# Power_BE.net
KiCad netlist of a schematic drawn in Altium Designer
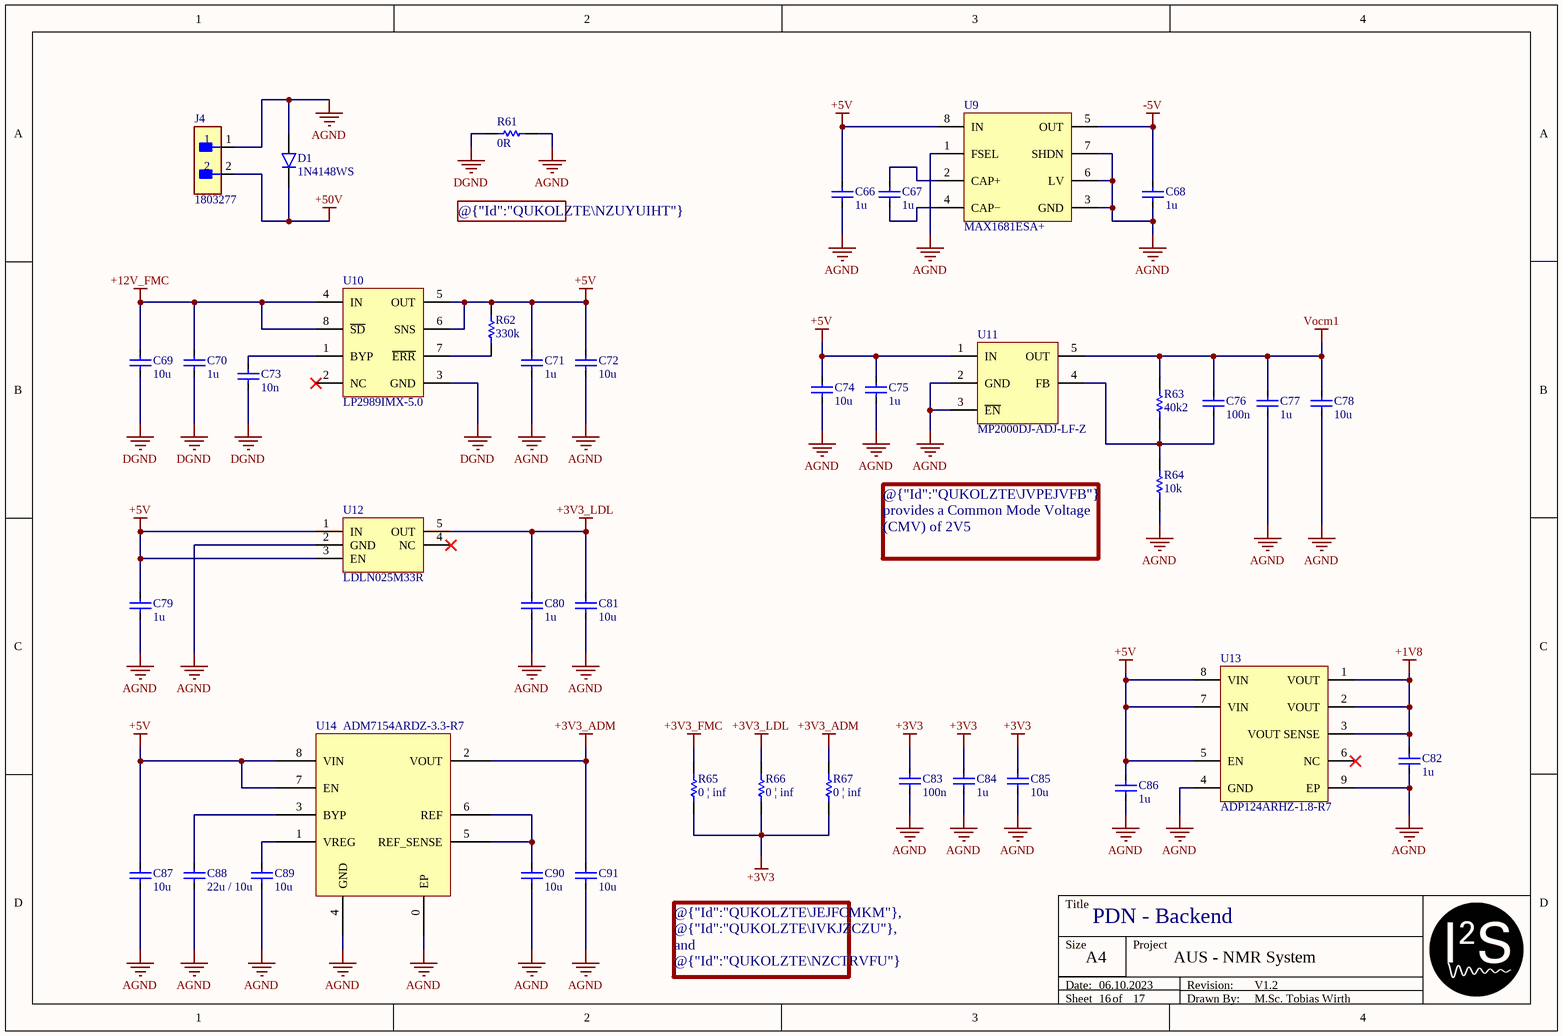
[diagram p0: Power_BE.SchDoc]

(export (version "E")
  (design (tool "Eeschema 10.0.6"))
  (components
    (comp (ref "C66") (value "1u") (footprint "CAP_0402") (libsource (lib "IIS-Lib_TW") (part "Cap")))
    (comp (ref "C67") (value "1u") (footprint "CAP_0402") (libsource (lib "IIS-Lib_TW") (part "Cap")))
    (comp (ref "C68") (value "1u") (footprint "CAP_0402") (libsource (lib "IIS-Lib_TW") (part "Cap")))
    (comp (ref "C69") (value "10u") (footprint "CAP_0603") (libsource (lib "IIS-Lib_TW") (part "Cap")))
    (comp (ref "C70") (value "1u") (footprint "CAP_0402") (libsource (lib "IIS-Lib_TW") (part "Cap")))
    (comp (ref "C71") (value "1u") (footprint "CAP_0402") (libsource (lib "IIS-Lib_TW") (part "Cap")))
    (comp (ref "C72") (value "10u") (footprint "CAP_0603") (libsource (lib "IIS-Lib_TW") (part "Cap")))
    (comp (ref "C73") (value "10n") (footprint "CAP_0402") (libsource (lib "IIS-Lib_TW") (part "Cap")))
    (comp (ref "C74") (value "10u") (footprint "CAP_0603") (libsource (lib "IIS-Lib_TW") (part "Cap")))
    (comp (ref "C75") (value "1u") (footprint "CAP_0402") (libsource (lib "IIS-Lib_TW") (part "Cap")))
    (comp (ref "C76") (value "100n") (footprint "CAP_0402") (libsource (lib "IIS-Lib_TW") (part "Cap")))
    (comp (ref "C77") (value "1u") (footprint "CAP_0402") (libsource (lib "IIS-Lib_TW") (part "Cap")))
    (comp (ref "C78") (value "10u") (footprint "CAP_0603") (libsource (lib "IIS-Lib_TW") (part "Cap")))
    (comp (ref "C79") (value "1u") (footprint "CAP_0402") (libsource (lib "IIS-Lib_TW") (part "Cap")))
    (comp (ref "C80") (value "1u") (footprint "CAP_0402") (libsource (lib "IIS-Lib_TW") (part "Cap")))
    (comp (ref "C81") (value "10u") (footprint "CAP_0603") (libsource (lib "IIS-Lib_TW") (part "Cap")))
    (comp (ref "C82") (value "1u") (footprint "CAP_0402") (libsource (lib "IIS-Lib_TW") (part "Cap")))
    (comp (ref "C83") (value "100n") (footprint "CAP_0402") (libsource (lib "IIS-Lib_TW") (part "Cap")))
    (comp (ref "C84") (value "1u") (footprint "CAP_0402") (libsource (lib "IIS-Lib_TW") (part "Cap")))
    (comp (ref "C85") (value "10u") (footprint "CAP_0603") (libsource (lib "IIS-Lib_TW") (part "Cap")))
    (comp (ref "C86") (value "1u") (footprint "CAP_0402") (libsource (lib "IIS-Lib_TW") (part "Cap")))
    (comp (ref "C87")
      (value "10u")
      (footprint "IIS-Lib_TW:CAP_0603")
      (libsource (lib "IIS-Lib_TW") (part "Cap"))
    )
    (comp (ref "C88")
      (value "22u / 10u")
      (footprint "IIS-Lib_TW:CAP_0603")
      (libsource (lib "IIS-Lib_TW") (part "Cap"))
    )
    (comp (ref "C89")
      (value "10u")
      (footprint "IIS-Lib_TW:CAP_0603")
      (libsource (lib "IIS-Lib_TW") (part "Cap"))
    )
    (comp (ref "C90")
      (value "10u")
      (footprint "IIS-Lib_TW:CAP_0603")
      (libsource (lib "IIS-Lib_TW") (part "Cap"))
    )
    (comp (ref "C91")
      (value "10u")
      (footprint "IIS-Lib_TW:CAP_0603")
      (libsource (lib "IIS-Lib_TW") (part "Cap"))
    )
    (comp (ref "D1") (value "1N4148WS") (footprint "SOD-123F") (libsource (lib "IIS-Lib_TW") (part "Diode")))
    (comp (ref "J4")
      (value "1803277")
      (footprint "Phoenix_MC1,5/2-G-3,81")
      (fields (field (name "MANUFACTURER") "Phoenix Contact"))
      (libsource (lib "IIS-Lib_TW") (part "Phoenix_MC1,5/2-G-3,81"))
    )
    (comp (ref "R61")
      (value "0R")
      (footprint "RES_0402")
      (description "Net tie")
      (libsource (lib "IIS-Lib_TW") (part "Res"))
    )
    (comp (ref "R62") (value "330k") (footprint "RES_0402") (libsource (lib "IIS-Lib_TW") (part "Res")))
    (comp (ref "R63") (value "40k2") (footprint "RES_0402") (libsource (lib "IIS-Lib_TW") (part "Res")))
    (comp (ref "R64") (value "10k") (footprint "RES_0402") (libsource (lib "IIS-Lib_TW") (part "Res")))
    (comp (ref "R65") (value "0 ¦ inf") (footprint "RES_0402") (libsource (lib "IIS-Lib_TW") (part "Res")))
    (comp (ref "R66") (value "0 ¦ inf") (footprint "RES_0402") (libsource (lib "IIS-Lib_TW") (part "Res")))
    (comp (ref "R67") (value "0 ¦ inf") (footprint "RES_0402") (libsource (lib "IIS-Lib_TW") (part "Res")))
    (comp (ref "U9")
      (value "MAX1681ESA+")
      (footprint "SOP127P600X175-8N")
      (description "125mA, Frequency-Selectable, Switched-Capacitor Voltage Converters")
      (libsource (lib "IIS-Lib_TW") (part "MAX1681"))
    )
    (comp (ref "U10")
      (value "LP2989IMX-5.0")
      (footprint "SOP127P600X175-8N")
      (libsource (lib "IIS-Lib_TW") (part "LP2989"))
    )
    (comp (ref "U11")
      (value "MP2000DJ-ADJ-LF-Z")
      (footprint "SOT95P280X145-5N")
      (libsource (lib "IIS-Lib_TW") (part "MP2000"))
    )
    (comp (ref "U12")
      (value "LDLN025M33R")
      (footprint "SOT95P280X145-5N")
      (libsource (lib "IIS-Lib_TW") (part "LDLN025"))
    )
    (comp (ref "U13")
      (value "ADP124ARHZ-1.8-R7")
      (footprint "IIS-Lib_TW:TSOP65P490X94_HS-9N - TW")
      (libsource (lib "IIS-Lib_TW") (part "ADP124"))
    )
    (comp (ref "U14")
      (value "ADM7154ARDZ-3.3-R7")
      (footprint "IIS-Lib_TW:SOIC-8_TP - TW")
      (libsource (lib "IIS-Lib_TW") (part "ADM715X"))
    )
  )
  (nets
    (net (code "1") (name "+1V8") (class "Default")
      (node (ref "C82") (pin "1") (pinfunction "1_1") (pintype "passive"))
      (node (ref "U13") (pin "1") (pinfunction "VOUT_1") (pintype "passive"))
      (node (ref "U13") (pin "2") (pinfunction "VOUT_2") (pintype "passive"))
      (node (ref "U13") (pin "3") (pinfunction "VOUT_SENSE_3") (pintype "passive"))
    )
    (net (code "2") (name "+3V3") (class "Default")
      (node (ref "C83") (pin "1") (pinfunction "1_1") (pintype "passive"))
      (node (ref "C84") (pin "1") (pinfunction "1_1") (pintype "passive"))
      (node (ref "C85") (pin "1") (pinfunction "1_1") (pintype "passive"))
      (node (ref "R65") (pin "1") (pinfunction "1_1") (pintype "passive"))
      (node (ref "R66") (pin "1") (pinfunction "1_1") (pintype "passive"))
      (node (ref "R67") (pin "1") (pinfunction "1_1") (pintype "passive"))
    )
    (net (code "3") (name "+3V3_ADM") (class "Default")
      (node (ref "C91") (pin "1") (pinfunction "1_1") (pintype "passive"))
      (node (ref "R67") (pin "2") (pinfunction "2_2") (pintype "passive"))
      (node (ref "U14") (pin "2") (pinfunction "VOUT_2") (pintype "passive"))
    )
    (net (code "4") (name "+3V3_FMC") (class "Default")
      (node (ref "R65") (pin "2") (pinfunction "2_2") (pintype "passive"))
    )
    (net (code "5") (name "+3V3_LDL") (class "Default")
      (node (ref "C80") (pin "1") (pinfunction "1_1") (pintype "passive"))
      (node (ref "C81") (pin "1") (pinfunction "1_1") (pintype "passive"))
      (node (ref "R66") (pin "2") (pinfunction "2_2") (pintype "passive"))
      (node (ref "U12") (pin "5") (pinfunction "OUT_5") (pintype "passive"))
    )
    (net (code "6") (name "+5V") (class "Default")
      (node (ref "C66") (pin "1") (pinfunction "1_1") (pintype "passive"))
      (node (ref "C71") (pin "1") (pinfunction "1_1") (pintype "passive"))
      (node (ref "C72") (pin "1") (pinfunction "1_1") (pintype "passive"))
      (node (ref "C74") (pin "1") (pinfunction "1_1") (pintype "passive"))
      (node (ref "C75") (pin "1") (pinfunction "1_1") (pintype "passive"))
      (node (ref "C79") (pin "1") (pinfunction "1_1") (pintype "passive"))
      (node (ref "C86") (pin "1") (pinfunction "1_1") (pintype "passive"))
      (node (ref "C87") (pin "1") (pinfunction "1_1") (pintype "passive"))
      (node (ref "R62") (pin "2") (pinfunction "2_2") (pintype "passive"))
      (node (ref "U10") (pin "5") (pinfunction "OUT_5") (pintype "passive"))
      (node (ref "U10") (pin "6") (pinfunction "SNS_6") (pintype "passive"))
      (node (ref "U11") (pin "1") (pinfunction "IN_1") (pintype "passive"))
      (node (ref "U12") (pin "1") (pinfunction "IN_1") (pintype "passive"))
      (node (ref "U12") (pin "3") (pinfunction "EN_3") (pintype "passive"))
      (node (ref "U13") (pin "5") (pinfunction "EN_5") (pintype "passive"))
      (node (ref "U13") (pin "7") (pinfunction "VIN_7") (pintype "passive"))
      (node (ref "U13") (pin "8") (pinfunction "VIN_8") (pintype "passive"))
      (node (ref "U14") (pin "7") (pinfunction "EN_7") (pintype "passive"))
      (node (ref "U14") (pin "8") (pinfunction "VIN_8") (pintype "passive"))
      (node (ref "U9") (pin "8") (pinfunction "IN_8") (pintype "passive"))
    )
    (net (code "7") (name "+12V_FMC") (class "Default")
      (node (ref "C69") (pin "1") (pinfunction "1_1") (pintype "passive"))
      (node (ref "C70") (pin "1") (pinfunction "1_1") (pintype "passive"))
      (node (ref "U10") (pin "4") (pinfunction "IN_4") (pintype "passive"))
      (node (ref "U10") (pin "8") (pinfunction "~{SD}_8") (pintype "passive"))
    )
    (net (code "8") (name "+50V") (class "Default")
      (node (ref "D1") (pin "2") (pinfunction "2_2") (pintype "passive"))
      (node (ref "J4") (pin "2") (pinfunction "2_2") (pintype "passive"))
    )
    (net (code "9") (name "-5V") (class "Default")
      (node (ref "C68") (pin "1") (pinfunction "1_1") (pintype "passive"))
      (node (ref "U9") (pin "5") (pinfunction "OUT_5") (pintype "passive"))
    )
    (net (code "10") (name "AGND") (class "Default")
      (node (ref "C66") (pin "2") (pinfunction "2_2") (pintype "passive"))
      (node (ref "C68") (pin "2") (pinfunction "2_2") (pintype "passive"))
      (node (ref "C71") (pin "2") (pinfunction "2_2") (pintype "passive"))
      (node (ref "C72") (pin "2") (pinfunction "2_2") (pintype "passive"))
      (node (ref "C74") (pin "2") (pinfunction "2_2") (pintype "passive"))
      (node (ref "C75") (pin "2") (pinfunction "2_2") (pintype "passive"))
      (node (ref "C77") (pin "2") (pinfunction "2_2") (pintype "passive"))
      (node (ref "C78") (pin "2") (pinfunction "2_2") (pintype "passive"))
      (node (ref "C79") (pin "2") (pinfunction "2_2") (pintype "passive"))
      (node (ref "C80") (pin "2") (pinfunction "2_2") (pintype "passive"))
      (node (ref "C81") (pin "2") (pinfunction "2_2") (pintype "passive"))
      (node (ref "C82") (pin "2") (pinfunction "2_2") (pintype "passive"))
      (node (ref "C83") (pin "2") (pinfunction "2_2") (pintype "passive"))
      (node (ref "C84") (pin "2") (pinfunction "2_2") (pintype "passive"))
      (node (ref "C85") (pin "2") (pinfunction "2_2") (pintype "passive"))
      (node (ref "C86") (pin "2") (pinfunction "2_2") (pintype "passive"))
      (node (ref "C87") (pin "2") (pinfunction "2_2") (pintype "passive"))
      (node (ref "C88") (pin "2") (pinfunction "2_2") (pintype "passive"))
      (node (ref "C89") (pin "2") (pinfunction "2_2") (pintype "passive"))
      (node (ref "C90") (pin "2") (pinfunction "2_2") (pintype "passive"))
      (node (ref "C91") (pin "2") (pinfunction "2_2") (pintype "passive"))
      (node (ref "D1") (pin "1") (pinfunction "1_1") (pintype "passive"))
      (node (ref "J4") (pin "1") (pinfunction "1_1") (pintype "passive"))
      (node (ref "R61") (pin "2") (pinfunction "2_2") (pintype "passive"))
      (node (ref "R64") (pin "1") (pinfunction "1_1") (pintype "passive"))
      (node (ref "U11") (pin "2") (pinfunction "GND_2") (pintype "passive"))
      (node (ref "U11") (pin "3") (pinfunction "~{EN}_3") (pintype "passive"))
      (node (ref "U12") (pin "2") (pinfunction "GND_2") (pintype "passive"))
      (node (ref "U13") (pin "4") (pinfunction "GND_4") (pintype "passive"))
      (node (ref "U13") (pin "9") (pinfunction "EP_9") (pintype "passive"))
      (node (ref "U14") (pin "0") (pinfunction "EP_0") (pintype "passive"))
      (node (ref "U14") (pin "4") (pinfunction "GND_4") (pintype "passive"))
      (node (ref "U9") (pin "1") (pinfunction "FSEL_1") (pintype "passive"))
      (node (ref "U9") (pin "3") (pinfunction "GND_3") (pintype "passive"))
      (node (ref "U9") (pin "6") (pinfunction "LV_6") (pintype "passive"))
      (node (ref "U9") (pin "7") (pinfunction "SHDN_7") (pintype "passive"))
    )
    (net (code "11") (name "DGND") (class "Default")
      (node (ref "C69") (pin "2") (pinfunction "2_2") (pintype "passive"))
      (node (ref "C70") (pin "2") (pinfunction "2_2") (pintype "passive"))
      (node (ref "C73") (pin "2") (pinfunction "2_2") (pintype "passive"))
      (node (ref "R61") (pin "1") (pinfunction "1_1") (pintype "passive"))
      (node (ref "U10") (pin "3") (pinfunction "GND_3") (pintype "passive"))
    )
    (net (code "12") (name "Net-(U9-CAP+)") (class "Default")
      (node (ref "C67") (pin "1") (pinfunction "1_1") (pintype "passive"))
      (node (ref "U9") (pin "2") (pinfunction "CAP+_2") (pintype "passive"))
    )
    (net (code "13") (name "Net-(U9-CAP−)") (class "Default")
      (node (ref "C67") (pin "2") (pinfunction "2_2") (pintype "passive"))
      (node (ref "U9") (pin "4") (pinfunction "CAP−_4") (pintype "passive"))
    )
    (net (code "14") (name "Net-(U10-BYP)") (class "Default")
      (node (ref "C73") (pin "1") (pinfunction "1_1") (pintype "passive"))
      (node (ref "U10") (pin "1") (pinfunction "BYP_1") (pintype "passive"))
    )
    (net (code "15") (name "Net-(U10-~{ERR})") (class "Default")
      (node (ref "R62") (pin "1") (pinfunction "1_1") (pintype "passive"))
      (node (ref "U10") (pin "7") (pinfunction "~{ERR}_7") (pintype "passive"))
    )
    (net (code "16") (name "Net-(U11-FB)") (class "Default")
      (node (ref "C76") (pin "2") (pinfunction "2_2") (pintype "passive"))
      (node (ref "R63") (pin "1") (pinfunction "1_1") (pintype "passive"))
      (node (ref "R64") (pin "2") (pinfunction "2_2") (pintype "passive"))
      (node (ref "U11") (pin "4") (pinfunction "FB_4") (pintype "passive"))
    )
    (net (code "17") (name "Net-(U14-BYP)") (class "Default")
      (node (ref "C88") (pin "1") (pinfunction "1_1") (pintype "passive"))
      (node (ref "U14") (pin "3") (pinfunction "BYP_3") (pintype "passive"))
    )
    (net (code "18") (name "Net-(U14-REF)") (class "Default")
      (node (ref "C90") (pin "1") (pinfunction "1_1") (pintype "passive"))
      (node (ref "U14") (pin "5") (pinfunction "REF_SENSE_5") (pintype "passive"))
      (node (ref "U14") (pin "6") (pinfunction "REF_6") (pintype "passive"))
    )
    (net (code "19") (name "Net-(U14-VREG)") (class "Default")
      (node (ref "C89") (pin "1") (pinfunction "1_1") (pintype "passive"))
      (node (ref "U14") (pin "1") (pinfunction "VREG_1") (pintype "passive"))
    )
    (net (code "20") (name "Vocm1") (class "Default")
      (node (ref "C76") (pin "1") (pinfunction "1_1") (pintype "passive"))
      (node (ref "C77") (pin "1") (pinfunction "1_1") (pintype "passive"))
      (node (ref "C78") (pin "1") (pinfunction "1_1") (pintype "passive"))
      (node (ref "R63") (pin "2") (pinfunction "2_2") (pintype "passive"))
      (node (ref "U11") (pin "5") (pinfunction "OUT_5") (pintype "passive"))
    )
    (net (code "21") (name "unconnected-(U10-NC-Pad2)") (class "Default")
      (node (ref "U10") (pin "2") (pinfunction "NC_2") (pintype "passive+no_connect"))
    )
    (net (code "22") (name "unconnected-(U12-NC-Pad4)") (class "Default")
      (node (ref "U12") (pin "4") (pinfunction "NC_4") (pintype "passive+no_connect"))
    )
    (net (code "23") (name "unconnected-(U13-NC-Pad6)") (class "Default")
      (node (ref "U13") (pin "6") (pinfunction "NC_6") (pintype "passive+no_connect"))
    )
  )
)
